# Fan-Module.net
KiCad netlist of a schematic drawn in EAGLE
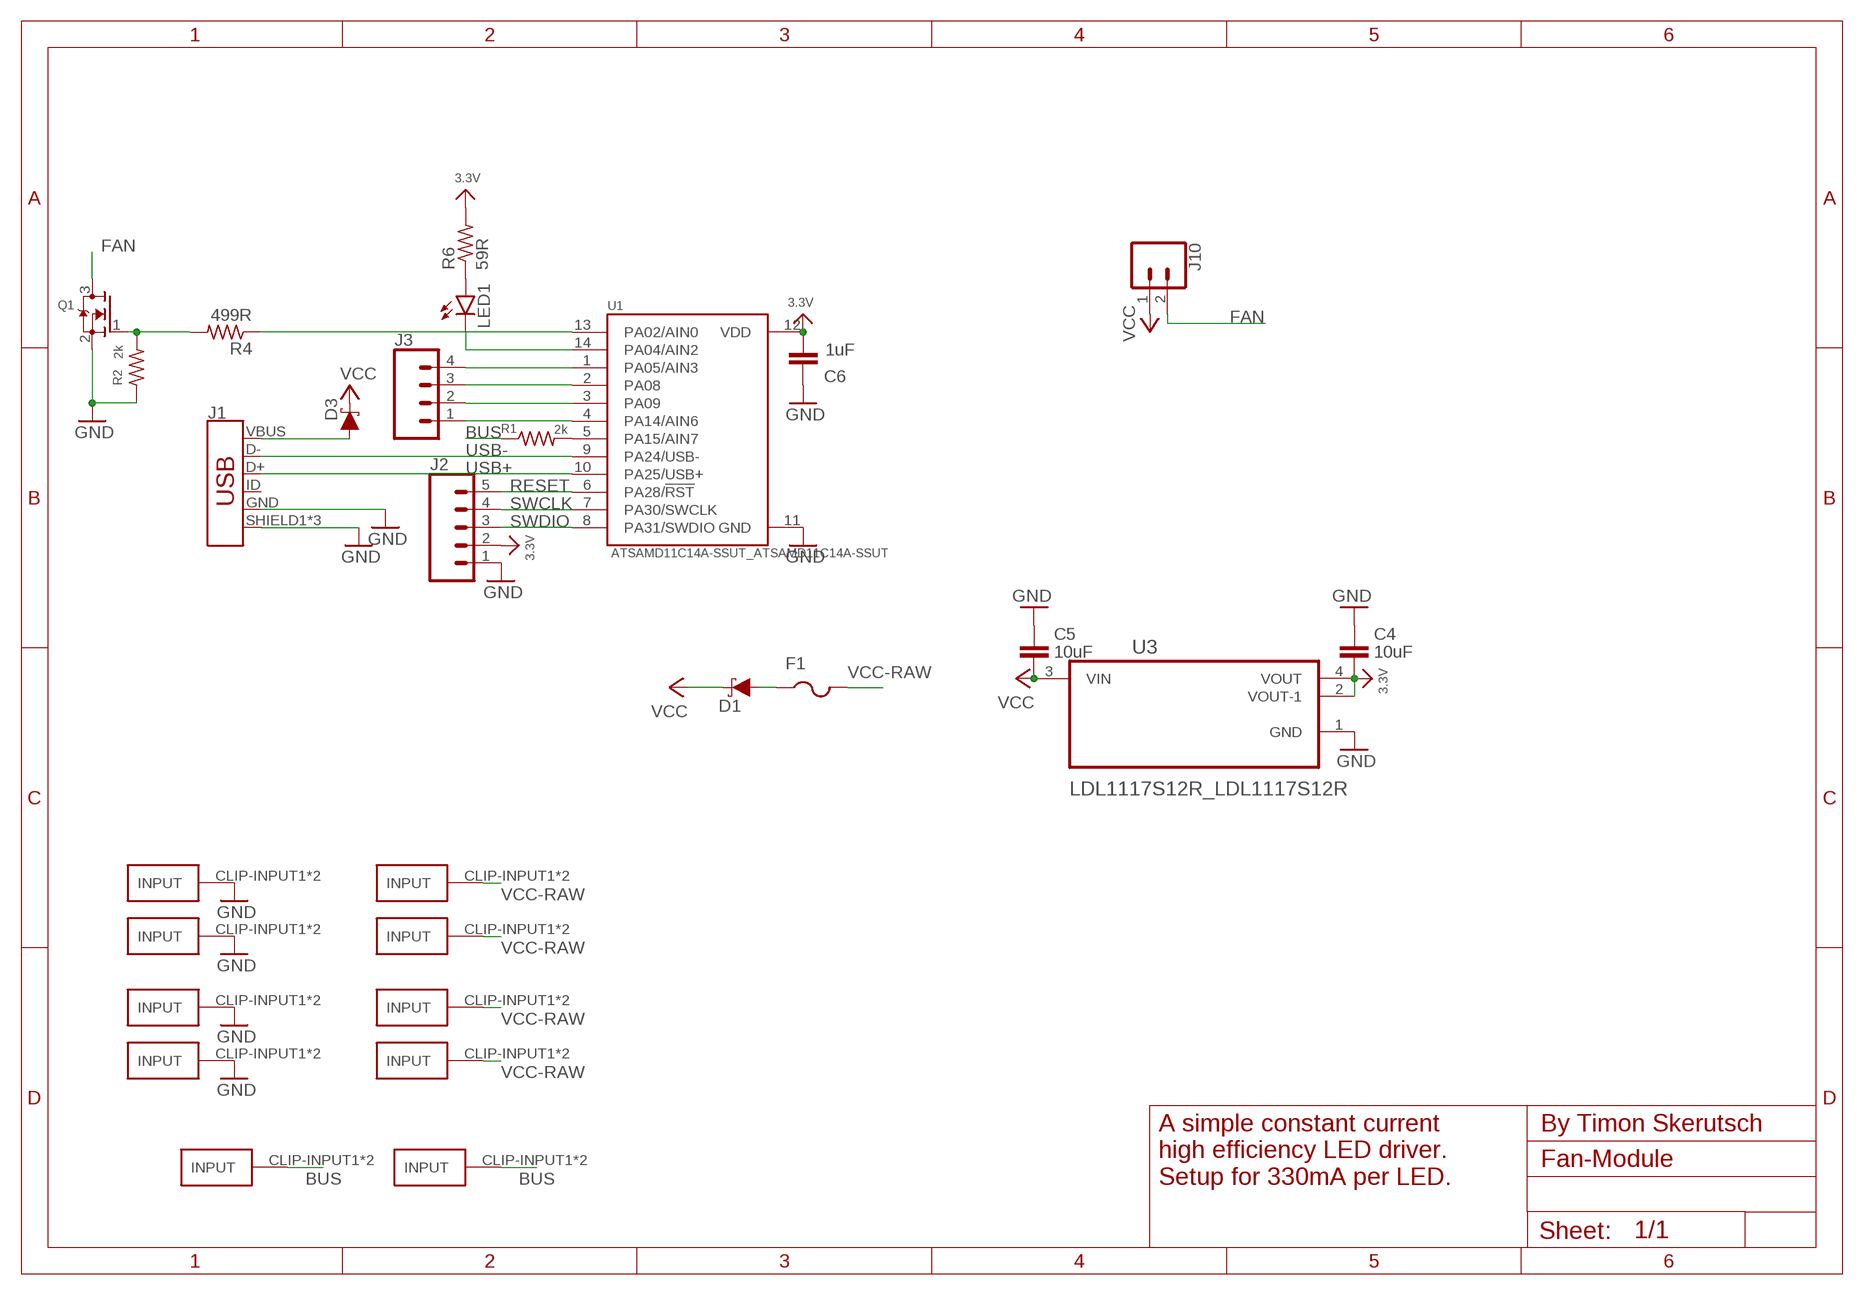
[diagram p0: schematic, sheet 1]

(export (version "E")
  (design (tool "Eeschema 10.0.6"))
  (components
    (comp (ref "C4")
      (value "10uF")
      (footprint "eagle-import:C0603")
      (libsource (lib "eagle-import") (part "C-EUC0603"))
    )
    (comp (ref "C5")
      (value "10uF")
      (footprint "eagle-import:C0603")
      (libsource (lib "eagle-import") (part "C-EUC0603"))
    )
    (comp (ref "C6")
      (value "1uF")
      (footprint "eagle-import:C0603")
      (libsource (lib "eagle-import") (part "C-EUC0603"))
    )
    (comp (ref "D1")
      (value "3A/40V/500mV")
      (footprint "eagle-import:SMA-DIODE")
      (libsource (lib "eagle-import") (part "DIODE-SCHOTTKY-B340A"))
    )
    (comp (ref "D3")
      (value "3A/40V/500mV")
      (footprint "eagle-import:SMA-DIODE")
      (libsource (lib "eagle-import") (part "DIODE-SCHOTTKY-B340A"))
    )
    (comp (ref "F1")
      (value "PTCFUSE-1812")
      (footprint "eagle-import:1812")
      (libsource (lib "eagle-import") (part "PTCFUSE-1812"))
    )
    (comp (ref "GND-CLIP")
      (value "FUSE-HOLDER-5X20MM")
      (footprint "eagle-import:FUSE-HOLDER-5X20MM")
      (libsource (lib "eagle-import") (part "FUSE-HOLDER-5X20MM"))
    )
    (comp (ref "GND-CLIP1")
      (value "FUSE-HOLDER-5X20MM")
      (footprint "eagle-import:FUSE-HOLDER-5X20MM")
      (libsource (lib "eagle-import") (part "FUSE-HOLDER-5X20MM"))
    )
    (comp (ref "GND-CLIP2")
      (value "FUSE-HOLDER-5X20MM")
      (footprint "eagle-import:FUSE-HOLDER-5X20MM")
      (libsource (lib "eagle-import") (part "FUSE-HOLDER-5X20MM"))
    )
    (comp (ref "GND-CLIP3")
      (value "FUSE-HOLDER-5X20MM")
      (footprint "eagle-import:FUSE-HOLDER-5X20MM")
      (libsource (lib "eagle-import") (part "FUSE-HOLDER-5X20MM"))
    )
    (comp (ref "J1")
      (value "USB_MICRO-B_FEMALE-SMT")
      (footprint "eagle-import:USB-B-MICRO-SMD")
      (libsource (lib "eagle-import") (part "USB_MICRO-B_FEMALE-SMT"))
    )
    (comp (ref "J2")
      (value "CONN_05")
      (footprint "eagle-import:1X05")
      (libsource (lib "eagle-import") (part "CONN_05"))
    )
    (comp (ref "J3")
      (value "CONN_04PTH")
      (footprint "eagle-import:1X04")
      (libsource (lib "eagle-import") (part "CONN_04PTH"))
    )
    (comp (ref "J10")
      (value "CONN_02PTH3")
      (footprint "eagle-import:1X02_LONGPADS")
      (libsource (lib "eagle-import") (part "CONN_02PTH3"))
    )
    (comp (ref "LED1")
      (value "LEDCHIPLED_0805")
      (footprint "eagle-import:CHIPLED_0805")
      (libsource (lib "eagle-import") (part "LEDCHIPLED_0805"))
    )
    (comp (ref "PWM-CLIP")
      (value "FUSE-HOLDER-5X20MM")
      (footprint "eagle-import:FUSE-HOLDER-5X20MM")
      (libsource (lib "eagle-import") (part "FUSE-HOLDER-5X20MM"))
    )
    (comp (ref "PWM-CLIP1")
      (value "FUSE-HOLDER-5X20MM")
      (footprint "eagle-import:FUSE-HOLDER-5X20MM")
      (libsource (lib "eagle-import") (part "FUSE-HOLDER-5X20MM"))
    )
    (comp (ref "Q1")
      (value "MOSFET-NWIDE")
      (footprint "eagle-import:SOT23-WIDE")
      (libsource (lib "eagle-import") (part "MOSFET-NWIDE"))
    )
    (comp (ref "R1")
      (value "2k")
      (footprint "eagle-import:R1206")
      (libsource (lib "eagle-import") (part "R-US_R1206"))
    )
    (comp (ref "R2")
      (value "2k")
      (footprint "eagle-import:R1206")
      (libsource (lib "eagle-import") (part "R-US_R1206"))
    )
    (comp (ref "R4")
      (value "499R")
      (footprint "eagle-import:R0805")
      (libsource (lib "eagle-import") (part "R-US_R0805"))
    )
    (comp (ref "R6")
      (value "59R")
      (footprint "eagle-import:R0805")
      (libsource (lib "eagle-import") (part "R-US_R0805"))
    )
    (comp (ref "U1")
      (value "ATSAMD11C14A-SSUT_ATSAMD11C14A-SSUT")
      (footprint "eagle-import:ATSAMD11C14A-SSUT_SOIC127P600X160-14N")
      (fields (field (name "MF") "Microchip") (field (name "MP") "ATSAMD11C14A-SSUT"))
      (libsource (lib "eagle-import") (part "ATSAMD11C14A-SSUT_ATSAMD11C14A-SSUT"))
    )
    (comp (ref "U3")
      (value "LDL1117S12R_LDL1117S12R")
      (footprint "eagle-import:LDL1117S12R_SOT230P700X180-4N")
      (fields (field (name "MF") "STMicroelectronics") (field (name "MP") "LDL1117S12R"))
      (libsource (lib "eagle-import") (part "LDL1117S12R_LDL1117S12R"))
    )
    (comp (ref "VCC-CLIP")
      (value "FUSE-HOLDER-5X20MM")
      (footprint "eagle-import:FUSE-HOLDER-5X20MM")
      (libsource (lib "eagle-import") (part "FUSE-HOLDER-5X20MM"))
    )
    (comp (ref "VCC-CLIP1")
      (value "FUSE-HOLDER-5X20MM")
      (footprint "eagle-import:FUSE-HOLDER-5X20MM")
      (libsource (lib "eagle-import") (part "FUSE-HOLDER-5X20MM"))
    )
    (comp (ref "VCC-CLIP2")
      (value "FUSE-HOLDER-5X20MM")
      (footprint "eagle-import:FUSE-HOLDER-5X20MM")
      (libsource (lib "eagle-import") (part "FUSE-HOLDER-5X20MM"))
    )
    (comp (ref "VCC-CLIP3")
      (value "FUSE-HOLDER-5X20MM")
      (footprint "eagle-import:FUSE-HOLDER-5X20MM")
      (libsource (lib "eagle-import") (part "FUSE-HOLDER-5X20MM"))
    )
  )
  (nets
    (net (code "1") (name "/BUS") (class "Default")
      (node (ref "PWM-CLIP") (pin "CLIP-INPUT1") (pinfunction "INPUT_CLIP-INPUT1") (pintype "bidirectional"))
      (node (ref "PWM-CLIP") (pin "CLIP-INPUT2") (pinfunction "INPUT_CLIP-INPUT2") (pintype "bidirectional"))
      (node (ref "PWM-CLIP1") (pin "CLIP-INPUT1") (pinfunction "INPUT_CLIP-INPUT1") (pintype "bidirectional"))
      (node (ref "PWM-CLIP1") (pin "CLIP-INPUT2") (pinfunction "INPUT_CLIP-INPUT2") (pintype "bidirectional"))
      (node (ref "R1") (pin "1") (pinfunction "1_1") (pintype "passive"))
    )
    (net (code "2") (name "/FAN") (class "Default")
      (node (ref "J10") (pin "2") (pinfunction "2_2") (pintype "passive"))
      (node (ref "Q1") (pin "3") (pinfunction "D_3") (pintype "bidirectional"))
    )
    (net (code "3") (name "/RESET") (class "Default")
      (node (ref "J2") (pin "5") (pinfunction "5_5") (pintype "passive"))
      (node (ref "U1") (pin "6") (pinfunction "PA28/~{RST}_6") (pintype "bidirectional"))
    )
    (net (code "4") (name "/SWCLK") (class "Default")
      (node (ref "J2") (pin "4") (pinfunction "4_4") (pintype "passive"))
      (node (ref "U1") (pin "7") (pinfunction "PA30/SWCLK_7") (pintype "bidirectional"))
    )
    (net (code "5") (name "/SWDIO") (class "Default")
      (node (ref "J2") (pin "3") (pinfunction "3_3") (pintype "passive"))
      (node (ref "U1") (pin "8") (pinfunction "PA31/SWDIO_8") (pintype "bidirectional"))
    )
    (net (code "6") (name "/USB+") (class "Default")
      (node (ref "J1") (pin "D+") (pinfunction "D+_D+") (pintype "bidirectional"))
      (node (ref "U1") (pin "10") (pinfunction "PA25/USB+_10") (pintype "bidirectional"))
    )
    (net (code "7") (name "/USB-") (class "Default")
      (node (ref "J1") (pin "D-") (pinfunction "D-_D-") (pintype "bidirectional"))
      (node (ref "U1") (pin "9") (pinfunction "PA24/USB-_9") (pintype "bidirectional"))
    )
    (net (code "8") (name "/VCC-RAW") (class "Default")
      (node (ref "F1") (pin "2") (pinfunction "2_2") (pintype "passive"))
      (node (ref "VCC-CLIP") (pin "CLIP-INPUT1") (pinfunction "INPUT_CLIP-INPUT1") (pintype "bidirectional"))
      (node (ref "VCC-CLIP") (pin "CLIP-INPUT2") (pinfunction "INPUT_CLIP-INPUT2") (pintype "bidirectional"))
      (node (ref "VCC-CLIP1") (pin "CLIP-INPUT1") (pinfunction "INPUT_CLIP-INPUT1") (pintype "bidirectional"))
      (node (ref "VCC-CLIP1") (pin "CLIP-INPUT2") (pinfunction "INPUT_CLIP-INPUT2") (pintype "bidirectional"))
      (node (ref "VCC-CLIP2") (pin "CLIP-INPUT1") (pinfunction "INPUT_CLIP-INPUT1") (pintype "bidirectional"))
      (node (ref "VCC-CLIP2") (pin "CLIP-INPUT2") (pinfunction "INPUT_CLIP-INPUT2") (pintype "bidirectional"))
      (node (ref "VCC-CLIP3") (pin "CLIP-INPUT1") (pinfunction "INPUT_CLIP-INPUT1") (pintype "bidirectional"))
      (node (ref "VCC-CLIP3") (pin "CLIP-INPUT2") (pinfunction "INPUT_CLIP-INPUT2") (pintype "bidirectional"))
    )
    (net (code "9") (name "3.3V") (class "Default")
      (node (ref "C4") (pin "2") (pinfunction "2_2") (pintype "passive"))
      (node (ref "C6") (pin "2") (pinfunction "2_2") (pintype "passive"))
      (node (ref "J2") (pin "2") (pinfunction "2_2") (pintype "passive"))
      (node (ref "R6") (pin "2") (pinfunction "2_2") (pintype "passive"))
      (node (ref "U1") (pin "12") (pinfunction "VDD_12") (pintype "power_in"))
      (node (ref "U3") (pin "2") (pinfunction "VOUT-1_2") (pintype "output"))
      (node (ref "U3") (pin "4") (pinfunction "VOUT_4") (pintype "output"))
    )
    (net (code "10") (name "GND") (class "Default")
      (node (ref "C4") (pin "1") (pinfunction "1_1") (pintype "passive"))
      (node (ref "C5") (pin "1") (pinfunction "1_1") (pintype "passive"))
      (node (ref "C6") (pin "1") (pinfunction "1_1") (pintype "passive"))
      (node (ref "GND-CLIP") (pin "CLIP-INPUT1") (pinfunction "INPUT_CLIP-INPUT1") (pintype "bidirectional"))
      (node (ref "GND-CLIP") (pin "CLIP-INPUT2") (pinfunction "INPUT_CLIP-INPUT2") (pintype "bidirectional"))
      (node (ref "GND-CLIP1") (pin "CLIP-INPUT1") (pinfunction "INPUT_CLIP-INPUT1") (pintype "bidirectional"))
      (node (ref "GND-CLIP1") (pin "CLIP-INPUT2") (pinfunction "INPUT_CLIP-INPUT2") (pintype "bidirectional"))
      (node (ref "GND-CLIP2") (pin "CLIP-INPUT1") (pinfunction "INPUT_CLIP-INPUT1") (pintype "bidirectional"))
      (node (ref "GND-CLIP2") (pin "CLIP-INPUT2") (pinfunction "INPUT_CLIP-INPUT2") (pintype "bidirectional"))
      (node (ref "GND-CLIP3") (pin "CLIP-INPUT1") (pinfunction "INPUT_CLIP-INPUT1") (pintype "bidirectional"))
      (node (ref "GND-CLIP3") (pin "CLIP-INPUT2") (pinfunction "INPUT_CLIP-INPUT2") (pintype "bidirectional"))
      (node (ref "J1") (pin "GND") (pinfunction "GND_GND") (pintype "power_in"))
      (node (ref "J1") (pin "SHIELD1") (pinfunction "SHIELD_SHIELD1") (pintype "bidirectional"))
      (node (ref "J1") (pin "SHIELD2") (pinfunction "SHIELD_SHIELD2") (pintype "bidirectional"))
      (node (ref "J1") (pin "SHIELD3") (pinfunction "SHIELD_SHIELD3") (pintype "bidirectional"))
      (node (ref "J2") (pin "1") (pinfunction "1_1") (pintype "passive"))
      (node (ref "Q1") (pin "2") (pinfunction "S_2") (pintype "bidirectional"))
      (node (ref "R2") (pin "1") (pinfunction "1_1") (pintype "passive"))
      (node (ref "U1") (pin "11") (pinfunction "GND_11") (pintype "power_in"))
      (node (ref "U3") (pin "1") (pinfunction "GND_1") (pintype "power_in"))
    )
    (net (code "11") (name "Net-(D1-PadA)") (class "Default")
      (node (ref "D1") (pin "A") (pinfunction "A_A") (pintype "passive"))
      (node (ref "F1") (pin "1") (pinfunction "1_1") (pintype "passive"))
    )
    (net (code "12") (name "Net-(D3-PadA)") (class "Default")
      (node (ref "D3") (pin "A") (pinfunction "A_A") (pintype "passive"))
      (node (ref "J1") (pin "VBUS") (pinfunction "VBUS_VBUS") (pintype "power_in"))
    )
    (net (code "13") (name "Net-(LED1-PadA)") (class "Default")
      (node (ref "LED1") (pin "A") (pinfunction "A_A") (pintype "passive"))
      (node (ref "R6") (pin "1") (pinfunction "1_1") (pintype "passive"))
    )
    (net (code "14") (name "Net-(Q1-G)") (class "Default")
      (node (ref "Q1") (pin "1") (pinfunction "G_1") (pintype "bidirectional"))
      (node (ref "R2") (pin "2") (pinfunction "2_2") (pintype "passive"))
      (node (ref "R4") (pin "2") (pinfunction "2_2") (pintype "passive"))
    )
    (net (code "15") (name "Net-(U1-PA02{slash}AIN0)") (class "Default")
      (node (ref "R4") (pin "1") (pinfunction "1_1") (pintype "passive"))
      (node (ref "U1") (pin "13") (pinfunction "PA02/AIN0_13") (pintype "bidirectional"))
    )
    (net (code "16") (name "Net-(U1-PA04{slash}AIN2)") (class "Default")
      (node (ref "LED1") (pin "C") (pinfunction "C_C") (pintype "passive"))
      (node (ref "U1") (pin "14") (pinfunction "PA04/AIN2_14") (pintype "bidirectional"))
    )
    (net (code "17") (name "Net-(U1-PA05{slash}AIN3)") (class "Default")
      (node (ref "J3") (pin "4") (pinfunction "4_4") (pintype "passive"))
      (node (ref "U1") (pin "1") (pinfunction "PA05/AIN3_1") (pintype "bidirectional"))
    )
    (net (code "18") (name "Net-(U1-PA08)") (class "Default")
      (node (ref "J3") (pin "3") (pinfunction "3_3") (pintype "passive"))
      (node (ref "U1") (pin "2") (pinfunction "PA08_2") (pintype "bidirectional"))
    )
    (net (code "19") (name "Net-(U1-PA09)") (class "Default")
      (node (ref "J3") (pin "2") (pinfunction "2_2") (pintype "passive"))
      (node (ref "U1") (pin "3") (pinfunction "PA09_3") (pintype "bidirectional"))
    )
    (net (code "20") (name "Net-(U1-PA14{slash}AIN6)") (class "Default")
      (node (ref "J3") (pin "1") (pinfunction "1_1") (pintype "passive"))
      (node (ref "U1") (pin "4") (pinfunction "PA14/AIN6_4") (pintype "bidirectional"))
    )
    (net (code "21") (name "Net-(U1-PA15{slash}AIN7)") (class "Default")
      (node (ref "R1") (pin "2") (pinfunction "2_2") (pintype "passive"))
      (node (ref "U1") (pin "5") (pinfunction "PA15/AIN7_5") (pintype "bidirectional"))
    )
    (net (code "22") (name "VCC") (class "Default")
      (node (ref "C5") (pin "2") (pinfunction "2_2") (pintype "passive"))
      (node (ref "D1") (pin "C") (pinfunction "C_C") (pintype "passive"))
      (node (ref "D3") (pin "C") (pinfunction "C_C") (pintype "passive"))
      (node (ref "J10") (pin "1") (pinfunction "1_1") (pintype "passive"))
      (node (ref "U3") (pin "3") (pinfunction "VIN_3") (pintype "input"))
    )
    (net (code "23") (name "unconnected-(J1-PadID)") (class "Default")
      (node (ref "J1") (pin "ID") (pinfunction "ID_ID") (pintype "bidirectional"))
    )
  )
)
